# tick-box-1591A-mk-1_0.net
KiCad netlist of a schematic drawn in EAGLE
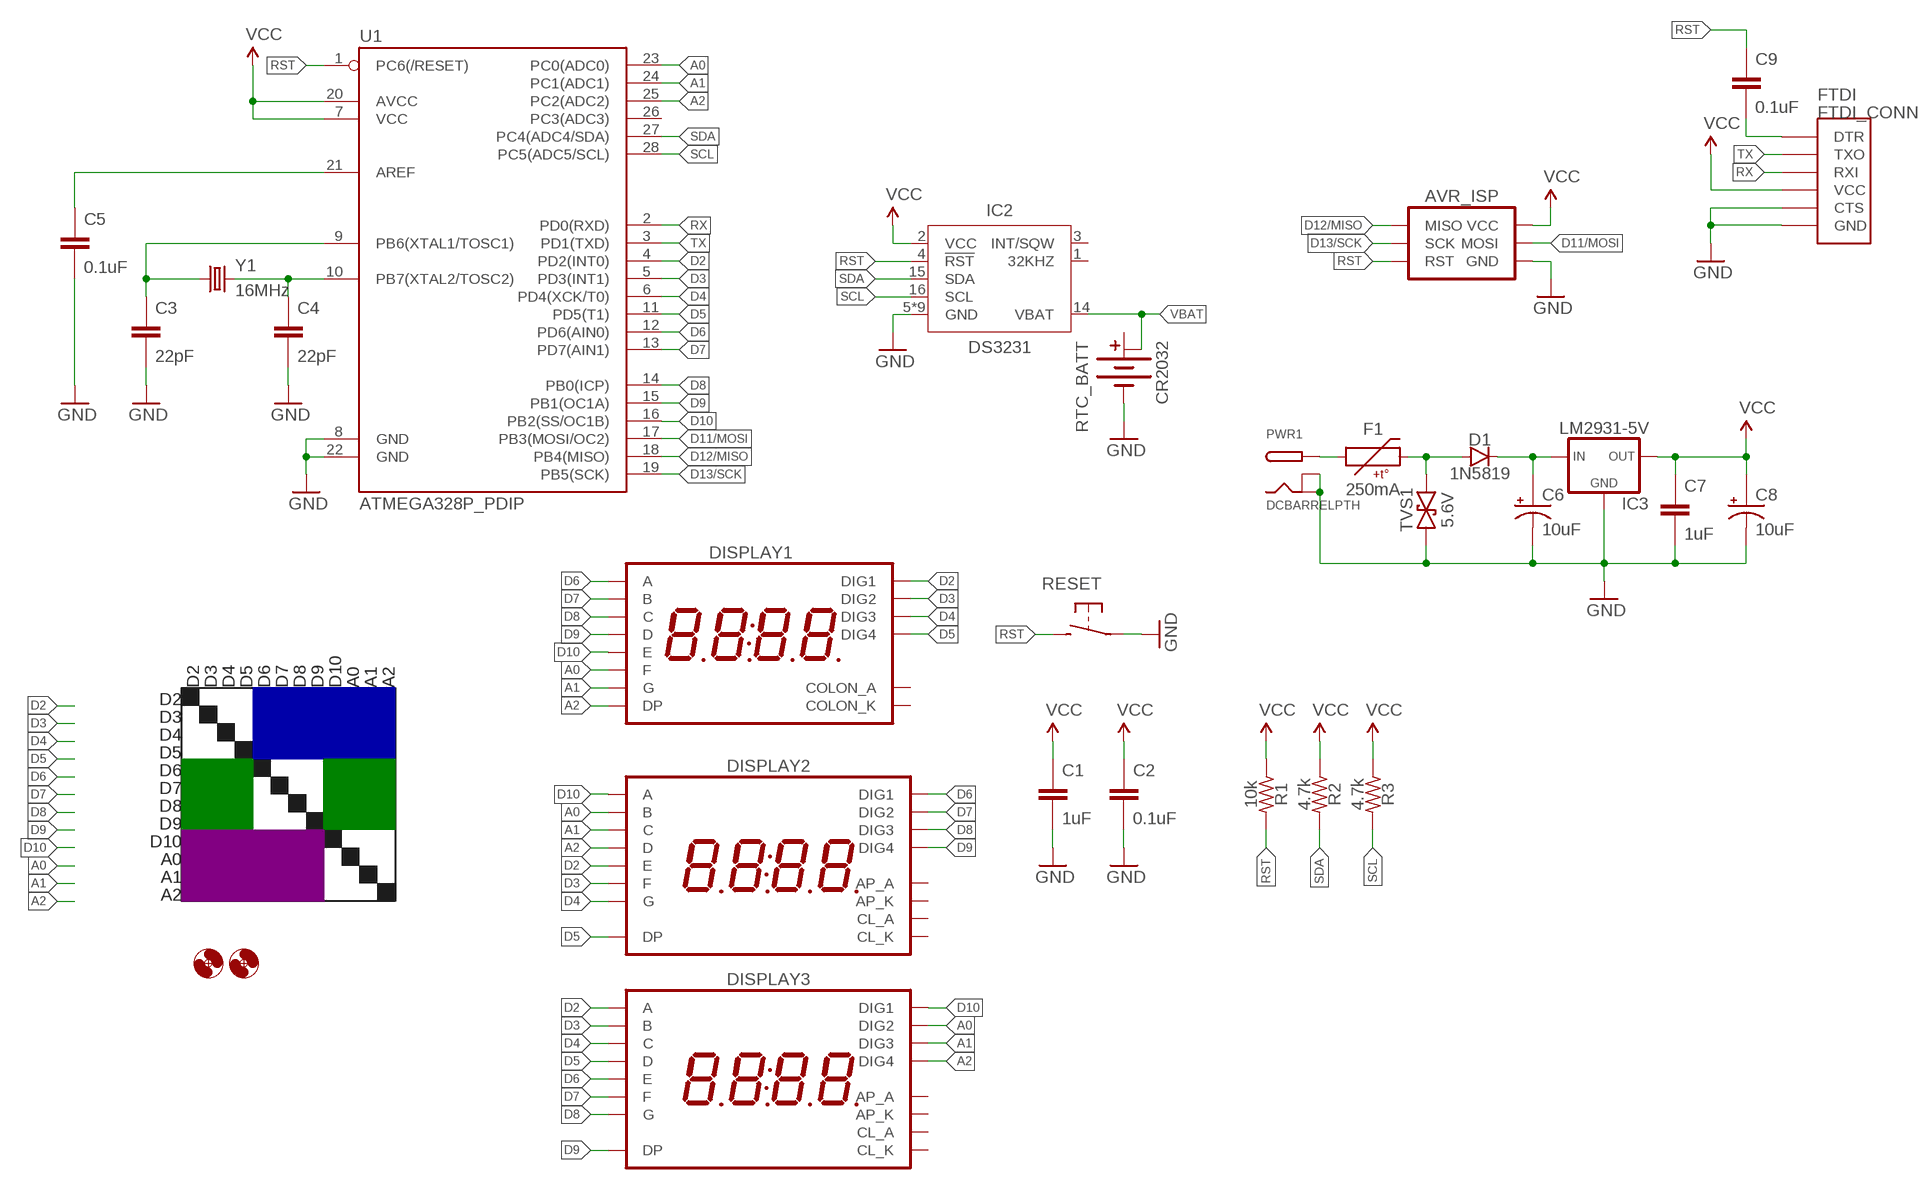
[diagram p0: schematic, sheet 1]

(export (version "E")
  (design (tool "Eeschema 10.0.6"))
  (components
    (comp (ref "AVR_ISP")
      (value "AVR_SPI_PRG_6PTH")
      (footprint "eagle-import:2X3")
      (libsource (lib "eagle-import") (part "AVR_SPI_PRG_6PTH"))
    )
    (comp (ref "C1")
      (value "1uF")
      (footprint "eagle-import:C025-024X044")
      (libsource (lib "eagle-import") (part "CAPACITOR-CERAMIC025-024X044"))
    )
    (comp (ref "C2")
      (value "0.1uF")
      (footprint "eagle-import:C025-024X044")
      (libsource (lib "eagle-import") (part "CAPACITOR-CERAMIC025-024X044"))
    )
    (comp (ref "C3")
      (value "22pF")
      (footprint "eagle-import:C025-024X044")
      (libsource (lib "eagle-import") (part "CAPACITOR-CERAMIC025-024X044"))
    )
    (comp (ref "C4")
      (value "22pF")
      (footprint "eagle-import:C025-024X044")
      (libsource (lib "eagle-import") (part "CAPACITOR-CERAMIC025-024X044"))
    )
    (comp (ref "C5")
      (value "0.1uF")
      (footprint "eagle-import:C025-024X044")
      (libsource (lib "eagle-import") (part "CAPACITOR-CERAMIC025-024X044"))
    )
    (comp (ref "C6")
      (value "10uF")
      (footprint "eagle-import:E2-5")
      (libsource (lib "eagle-import") (part "CAPACITOR-POLARIZEDE2-5"))
    )
    (comp (ref "C7")
      (value "1uF")
      (footprint "eagle-import:C025-024X044")
      (libsource (lib "eagle-import") (part "CAPACITOR-CERAMIC025-024X044"))
    )
    (comp (ref "C8")
      (value "10uF")
      (footprint "eagle-import:E2-5")
      (libsource (lib "eagle-import") (part "CAPACITOR-POLARIZEDE2-5"))
    )
    (comp (ref "C9")
      (value "0.1uF")
      (footprint "eagle-import:C025-024X044")
      (libsource (lib "eagle-import") (part "CAPACITOR-CERAMIC025-024X044"))
    )
    (comp (ref "D1")
      (value "1N5819")
      (footprint "eagle-import:DIODE-10.16MM")
      (libsource (lib "eagle-import") (part "DIODEPTH-10.68MM"))
    )
    (comp (ref "DISPLAY1")
      (value "7SEG_4DIGIT_COLON14.2MM-CC-NS")
      (footprint "eagle-import:7SEG_4DIG_NS")
      (libsource (lib "eagle-import") (part "7SEG_4DIGIT_COLON14.2MM-CC-NS"))
    )
    (comp (ref "DISPLAY2")
      (value "7SEG_4DIGIT_COLON_APOS")
      (footprint "eagle-import:7SEG_4DIG_10MM")
      (libsource (lib "eagle-import") (part "7SEG_4DIGIT_COLON_APOS"))
    )
    (comp (ref "DISPLAY3")
      (value "7SEG_4DIGIT_COLON_APOS")
      (footprint "eagle-import:7SEG_4DIG_10MM")
      (libsource (lib "eagle-import") (part "7SEG_4DIGIT_COLON_APOS"))
    )
    (comp (ref "F1")
      (value "250mA")
      (footprint "eagle-import:PTC-PTH-5.08MM")
      (libsource (lib "eagle-import") (part "PTCPTH-5.08MM"))
    )
    (comp (ref "FTDI")
      (value "FTDI_CONN")
      (footprint "eagle-import:FTDI_CONN")
      (libsource (lib "eagle-import") (part "FTDI_CONN"))
    )
    (comp (ref "H1")
      (value "HOLE#2")
      (footprint "eagle-import:HOLE-#2")
      (libsource (lib "eagle-import") (part "HOLE#2"))
    )
    (comp (ref "H2")
      (value "HOLE#2")
      (footprint "eagle-import:HOLE-#2")
      (libsource (lib "eagle-import") (part "HOLE#2"))
    )
    (comp (ref "IC2")
      (value "DS3231")
      (footprint "eagle-import:SO16W")
      (libsource (lib "eagle-import") (part "DS3231"))
    )
    (comp (ref "IC3")
      (value "LM2931-5V")
      (footprint "eagle-import:TO-92-AMMO")
      (libsource (lib "eagle-import") (part "V_REG_78XXTO-92-INLINE"))
    )
    (comp (ref "PWR1")
      (value "DCBARRELPTH")
      (footprint "eagle-import:DCJACK_2MM_PTH")
      (libsource (lib "eagle-import") (part "DCBARRELPTH"))
    )
    (comp (ref "R1")
      (value "10k")
      (footprint "eagle-import:RESISTOR-AXIAL-PTH-7.62MM")
      (libsource (lib "eagle-import") (part "RESISTORPTH-AXIAL-7.62MM"))
    )
    (comp (ref "R2")
      (value "4.7k")
      (footprint "eagle-import:RESISTOR-AXIAL-PTH-7.62MM")
      (libsource (lib "eagle-import") (part "RESISTORPTH-AXIAL-7.62MM"))
    )
    (comp (ref "R3")
      (value "4.7k")
      (footprint "eagle-import:RESISTOR-AXIAL-PTH-7.62MM")
      (libsource (lib "eagle-import") (part "RESISTORPTH-AXIAL-7.62MM"))
    )
    (comp (ref "RESET")
      (value "SPST-NO-TACT6MM-PTH-SMALL-PADS")
      (footprint "eagle-import:DTS-6-SMALL-PADS")
      (libsource (lib "eagle-import") (part "SPST-NO-TACT6MM-PTH-SMALL-PADS"))
    )
    (comp (ref "RTC_BATT")
      (value "CR2032")
      (footprint "eagle-import:BATTCON_20MM_MINE")
      (libsource (lib "eagle-import") (part "BATTERY-COINCR2032_SMD"))
    )
    (comp (ref "TVS1")
      (value "5.6V")
      (footprint "eagle-import:DO-41-TVS")
      (libsource (lib "eagle-import") (part "TVSDO-41-TVS-BIDIRECTIONAL"))
    )
    (comp (ref "U1")
      (value "ATMEGA328P_PDIP")
      (footprint "eagle-import:DIL28-3")
      (libsource (lib "eagle-import") (part "ATMEGA328P_PDIP"))
    )
    (comp (ref "Y1")
      (value "16MHz")
      (footprint "eagle-import:HC49U-V")
      (libsource (lib "eagle-import") (part "CRYSTALHC49UV"))
    )
  )
  (nets
    (net (code "1") (name "A0") (class "Default")
      (node (ref "DISPLAY1") (pin "P$12") (pinfunction "F_P$12") (pintype "passive"))
      (node (ref "DISPLAY2") (pin "16") (pinfunction "B_16") (pintype "passive"))
      (node (ref "DISPLAY3") (pin "2") (pinfunction "DIG2_2") (pintype "passive"))
      (node (ref "U1") (pin "23") (pinfunction "PC0(ADC0)_23") (pintype "bidirectional"))
    )
    (net (code "2") (name "A1") (class "Default")
      (node (ref "DISPLAY1") (pin "P$5") (pinfunction "G_P$5") (pintype "passive"))
      (node (ref "DISPLAY2") (pin "13") (pinfunction "C_13") (pintype "passive"))
      (node (ref "DISPLAY3") (pin "6") (pinfunction "DIG3_6") (pintype "passive"))
      (node (ref "U1") (pin "24") (pinfunction "PC1(ADC1)_24") (pintype "bidirectional"))
    )
    (net (code "3") (name "A2") (class "Default")
      (node (ref "DISPLAY1") (pin "P$3") (pinfunction "DP_P$3") (pintype "passive"))
      (node (ref "DISPLAY2") (pin "3") (pinfunction "D_3") (pintype "passive"))
      (node (ref "DISPLAY3") (pin "8") (pinfunction "DIG4_8") (pintype "passive"))
      (node (ref "U1") (pin "25") (pinfunction "PC2(ADC2)_25") (pintype "bidirectional"))
    )
    (net (code "4") (name "D2") (class "Default")
      (node (ref "DISPLAY1") (pin "P$14") (pinfunction "DIG1_P$14") (pintype "passive"))
      (node (ref "DISPLAY2") (pin "5") (pinfunction "E_5") (pintype "passive"))
      (node (ref "DISPLAY3") (pin "14") (pinfunction "A_14") (pintype "passive"))
      (node (ref "U1") (pin "4") (pinfunction "PD2(INT0)_4") (pintype "bidirectional"))
    )
    (net (code "5") (name "D3") (class "Default")
      (node (ref "DISPLAY1") (pin "P$11") (pinfunction "DIG2_P$11") (pintype "passive"))
      (node (ref "DISPLAY2") (pin "11") (pinfunction "F_11") (pintype "passive"))
      (node (ref "DISPLAY3") (pin "16") (pinfunction "B_16") (pintype "passive"))
      (node (ref "U1") (pin "5") (pinfunction "PD3(INT1)_5") (pintype "bidirectional"))
    )
    (net (code "6") (name "D4") (class "Default")
      (node (ref "DISPLAY1") (pin "P$10") (pinfunction "DIG3_P$10") (pintype "passive"))
      (node (ref "DISPLAY2") (pin "15") (pinfunction "G_15") (pintype "passive"))
      (node (ref "DISPLAY3") (pin "13") (pinfunction "C_13") (pintype "passive"))
      (node (ref "U1") (pin "6") (pinfunction "PD4(XCK/T0)_6") (pintype "bidirectional"))
    )
    (net (code "7") (name "D5") (class "Default")
      (node (ref "DISPLAY1") (pin "P$6") (pinfunction "DIG4_P$6") (pintype "passive"))
      (node (ref "DISPLAY2") (pin "7") (pinfunction "DP_7") (pintype "passive"))
      (node (ref "DISPLAY3") (pin "3") (pinfunction "D_3") (pintype "passive"))
      (node (ref "U1") (pin "11") (pinfunction "PD5(T1)_11") (pintype "bidirectional"))
    )
    (net (code "8") (name "D6") (class "Default")
      (node (ref "DISPLAY1") (pin "P$13") (pinfunction "A_P$13") (pintype "passive"))
      (node (ref "DISPLAY2") (pin "1") (pinfunction "DIG1_1") (pintype "passive"))
      (node (ref "DISPLAY3") (pin "5") (pinfunction "E_5") (pintype "passive"))
      (node (ref "U1") (pin "12") (pinfunction "PD6(AIN0)_12") (pintype "bidirectional"))
    )
    (net (code "9") (name "D7") (class "Default")
      (node (ref "DISPLAY1") (pin "P$9") (pinfunction "B_P$9") (pintype "passive"))
      (node (ref "DISPLAY2") (pin "2") (pinfunction "DIG2_2") (pintype "passive"))
      (node (ref "DISPLAY3") (pin "11") (pinfunction "F_11") (pintype "passive"))
      (node (ref "U1") (pin "13") (pinfunction "PD7(AIN1)_13") (pintype "bidirectional"))
    )
    (net (code "10") (name "D8") (class "Default")
      (node (ref "DISPLAY1") (pin "P$4") (pinfunction "C_P$4") (pintype "passive"))
      (node (ref "DISPLAY2") (pin "6") (pinfunction "DIG3_6") (pintype "passive"))
      (node (ref "DISPLAY3") (pin "15") (pinfunction "G_15") (pintype "passive"))
      (node (ref "U1") (pin "14") (pinfunction "PB0(ICP)_14") (pintype "bidirectional"))
    )
    (net (code "11") (name "D9") (class "Default")
      (node (ref "DISPLAY1") (pin "P$2") (pinfunction "D_P$2") (pintype "passive"))
      (node (ref "DISPLAY2") (pin "8") (pinfunction "DIG4_8") (pintype "passive"))
      (node (ref "DISPLAY3") (pin "7") (pinfunction "DP_7") (pintype "passive"))
      (node (ref "U1") (pin "15") (pinfunction "PB1(OC1A)_15") (pintype "bidirectional"))
    )
    (net (code "12") (name "D10") (class "Default")
      (node (ref "DISPLAY1") (pin "P$1") (pinfunction "E_P$1") (pintype "passive"))
      (node (ref "DISPLAY2") (pin "14") (pinfunction "A_14") (pintype "passive"))
      (node (ref "DISPLAY3") (pin "1") (pinfunction "DIG1_1") (pintype "passive"))
      (node (ref "U1") (pin "16") (pinfunction "PB2(SS/OC1B)_16") (pintype "bidirectional"))
    )
    (net (code "13") (name "D11{slash}MOSI") (class "Default")
      (node (ref "AVR_ISP") (pin "4") (pinfunction "MOSI_4") (pintype "passive"))
      (node (ref "U1") (pin "17") (pinfunction "PB3(MOSI/OC2)_17") (pintype "bidirectional"))
    )
    (net (code "14") (name "D12{slash}MISO") (class "Default")
      (node (ref "AVR_ISP") (pin "1") (pinfunction "MISO_1") (pintype "passive"))
      (node (ref "U1") (pin "18") (pinfunction "PB4(MISO)_18") (pintype "bidirectional"))
    )
    (net (code "15") (name "D13{slash}SCK") (class "Default")
      (node (ref "AVR_ISP") (pin "3") (pinfunction "SCK_3") (pintype "passive"))
      (node (ref "U1") (pin "19") (pinfunction "PB5(SCK)_19") (pintype "bidirectional"))
    )
    (net (code "16") (name "GND") (class "Default")
      (node (ref "AVR_ISP") (pin "6") (pinfunction "GND_6") (pintype "passive"))
      (node (ref "C1") (pin "2") (pinfunction "2_2") (pintype "passive"))
      (node (ref "C2") (pin "2") (pinfunction "2_2") (pintype "passive"))
      (node (ref "C3") (pin "2") (pinfunction "2_2") (pintype "passive"))
      (node (ref "C4") (pin "2") (pinfunction "2_2") (pintype "passive"))
      (node (ref "C5") (pin "2") (pinfunction "2_2") (pintype "passive"))
      (node (ref "C6") (pin "-") (pinfunction "-_-") (pintype "passive"))
      (node (ref "C7") (pin "2") (pinfunction "2_2") (pintype "passive"))
      (node (ref "C8") (pin "-") (pinfunction "-_-") (pintype "passive"))
      (node (ref "FTDI") (pin "CTS") (pinfunction "CTS_CTS") (pintype "bidirectional"))
      (node (ref "FTDI") (pin "GND") (pinfunction "GND_GND") (pintype "bidirectional"))
      (node (ref "IC2") (pin "10") (pinfunction "GND_10") (pintype "bidirectional"))
      (node (ref "IC2") (pin "11") (pinfunction "GND_11") (pintype "bidirectional"))
      (node (ref "IC2") (pin "12") (pinfunction "GND_12") (pintype "bidirectional"))
      (node (ref "IC2") (pin "13") (pinfunction "GND_13") (pintype "bidirectional"))
      (node (ref "IC2") (pin "5") (pinfunction "GND_5") (pintype "bidirectional"))
      (node (ref "IC2") (pin "6") (pinfunction "GND_6") (pintype "bidirectional"))
      (node (ref "IC2") (pin "7") (pinfunction "GND_7") (pintype "bidirectional"))
      (node (ref "IC2") (pin "8") (pinfunction "GND_8") (pintype "bidirectional"))
      (node (ref "IC2") (pin "9") (pinfunction "GND_9") (pintype "bidirectional"))
      (node (ref "IC3") (pin "2") (pinfunction "GND_2") (pintype "bidirectional"))
      (node (ref "PWR1") (pin "BRK") (pinfunction "BRK_BRK") (pintype "bidirectional"))
      (node (ref "PWR1") (pin "GND") (pinfunction "GND_GND") (pintype "bidirectional"))
      (node (ref "RESET") (pin "1") (pinfunction "1_1") (pintype "passive"))
      (node (ref "RESET") (pin "2") (pinfunction "1_2") (pintype "passive"))
      (node (ref "RTC_BATT") (pin "BOTTOM") (pinfunction "-_BOTTOM") (pintype "bidirectional"))
      (node (ref "TVS1") (pin "P$1") (pinfunction "1_P$1") (pintype "passive"))
      (node (ref "U1") (pin "22") (pinfunction "GND_22") (pintype "bidirectional"))
      (node (ref "U1") (pin "8") (pinfunction "GND_8") (pintype "bidirectional"))
    )
    (net (code "17") (name "Net-(C9-Pad2)") (class "Default")
      (node (ref "C9") (pin "2") (pinfunction "2_2") (pintype "passive"))
      (node (ref "FTDI") (pin "DTR") (pinfunction "DTR_DTR") (pintype "bidirectional"))
    )
    (net (code "18") (name "Net-(F1-1)") (class "Default")
      (node (ref "F1") (pin "P$1") (pinfunction "1_P$1") (pintype "passive"))
      (node (ref "PWR1") (pin "PWR") (pinfunction "PWR_PWR") (pintype "bidirectional"))
    )
    (net (code "19") (name "Net-(F1-2)") (class "Default")
      (node (ref "D1") (pin "A") (pinfunction "A_A") (pintype "passive"))
      (node (ref "F1") (pin "P$2") (pinfunction "2_P$2") (pintype "passive"))
      (node (ref "TVS1") (pin "P$2") (pinfunction "2_P$2") (pintype "passive"))
    )
    (net (code "20") (name "Net-(IC3-IN)") (class "Default")
      (node (ref "C6") (pin "+") (pinfunction "+_+") (pintype "passive"))
      (node (ref "D1") (pin "C") (pinfunction "C_C") (pintype "passive"))
      (node (ref "IC3") (pin "1") (pinfunction "IN_1") (pintype "bidirectional"))
    )
    (net (code "21") (name "Net-(U1-AREF)") (class "Default")
      (node (ref "C5") (pin "1") (pinfunction "1_1") (pintype "passive"))
      (node (ref "U1") (pin "21") (pinfunction "AREF_21") (pintype "bidirectional"))
    )
    (net (code "22") (name "Net-(U1-PB6(XTAL1{slash}TOSC1))") (class "Default")
      (node (ref "C3") (pin "1") (pinfunction "1_1") (pintype "passive"))
      (node (ref "U1") (pin "9") (pinfunction "PB6(XTAL1/TOSC1)_9") (pintype "bidirectional"))
      (node (ref "Y1") (pin "1") (pinfunction "1_1") (pintype "passive"))
    )
    (net (code "23") (name "Net-(U1-PB7(XTAL2{slash}TOSC2))") (class "Default")
      (node (ref "C4") (pin "1") (pinfunction "1_1") (pintype "passive"))
      (node (ref "U1") (pin "10") (pinfunction "PB7(XTAL2/TOSC2)_10") (pintype "bidirectional"))
      (node (ref "Y1") (pin "2") (pinfunction "2_2") (pintype "passive"))
    )
    (net (code "24") (name "RST") (class "Default")
      (node (ref "AVR_ISP") (pin "5") (pinfunction "RST_5") (pintype "passive"))
      (node (ref "C9") (pin "1") (pinfunction "1_1") (pintype "passive"))
      (node (ref "IC2") (pin "4") (pinfunction "~{RST}_4") (pintype "bidirectional"))
      (node (ref "R1") (pin "P$2") (pinfunction "2_P$2") (pintype "passive"))
      (node (ref "RESET") (pin "3") (pinfunction "2_3") (pintype "passive"))
      (node (ref "RESET") (pin "4") (pinfunction "2_4") (pintype "passive"))
      (node (ref "U1") (pin "1") (pinfunction "PC6(/RESET)_1") (pintype "bidirectional"))
    )
    (net (code "25") (name "RX") (class "Default")
      (node (ref "FTDI") (pin "RXI") (pinfunction "RXI_RXI") (pintype "bidirectional"))
      (node (ref "U1") (pin "2") (pinfunction "PD0(RXD)_2") (pintype "bidirectional"))
    )
    (net (code "26") (name "SCL") (class "Default")
      (node (ref "IC2") (pin "16") (pinfunction "SCL_16") (pintype "bidirectional"))
      (node (ref "R3") (pin "P$2") (pinfunction "2_P$2") (pintype "passive"))
      (node (ref "U1") (pin "28") (pinfunction "PC5(ADC5/SCL)_28") (pintype "bidirectional"))
    )
    (net (code "27") (name "SDA") (class "Default")
      (node (ref "IC2") (pin "15") (pinfunction "SDA_15") (pintype "bidirectional"))
      (node (ref "R2") (pin "P$2") (pinfunction "2_P$2") (pintype "passive"))
      (node (ref "U1") (pin "27") (pinfunction "PC4(ADC4/SDA)_27") (pintype "bidirectional"))
    )
    (net (code "28") (name "TX") (class "Default")
      (node (ref "FTDI") (pin "TXO") (pinfunction "TXO_TXO") (pintype "bidirectional"))
      (node (ref "U1") (pin "3") (pinfunction "PD1(TXD)_3") (pintype "bidirectional"))
    )
    (net (code "29") (name "VBAT") (class "Default")
      (node (ref "IC2") (pin "14") (pinfunction "VBAT_14") (pintype "bidirectional"))
      (node (ref "RTC_BATT") (pin "TOP@2") (pinfunction "+1_TOP@2") (pintype "bidirectional"))
    )
    (net (code "30") (name "VCC") (class "Default")
      (node (ref "AVR_ISP") (pin "2") (pinfunction "VCC_2") (pintype "passive"))
      (node (ref "C1") (pin "1") (pinfunction "1_1") (pintype "passive"))
      (node (ref "C2") (pin "1") (pinfunction "1_1") (pintype "passive"))
      (node (ref "C7") (pin "1") (pinfunction "1_1") (pintype "passive"))
      (node (ref "C8") (pin "+") (pinfunction "+_+") (pintype "passive"))
      (node (ref "FTDI") (pin "VCC") (pinfunction "VCC_VCC") (pintype "bidirectional"))
      (node (ref "IC2") (pin "2") (pinfunction "VCC_2") (pintype "bidirectional"))
      (node (ref "IC3") (pin "3") (pinfunction "OUT_3") (pintype "bidirectional"))
      (node (ref "R1") (pin "P$1") (pinfunction "1_P$1") (pintype "passive"))
      (node (ref "R2") (pin "P$1") (pinfunction "1_P$1") (pintype "passive"))
      (node (ref "R3") (pin "P$1") (pinfunction "1_P$1") (pintype "passive"))
      (node (ref "U1") (pin "20") (pinfunction "AVCC_20") (pintype "bidirectional"))
      (node (ref "U1") (pin "7") (pinfunction "VCC_7") (pintype "bidirectional"))
    )
    (net (code "31") (name "unconnected-(DISPLAY1-COLON_A-PadP$8)") (class "Default")
      (node (ref "DISPLAY1") (pin "P$8") (pinfunction "COLON_A_P$8") (pintype "passive"))
    )
    (net (code "32") (name "unconnected-(DISPLAY1-COLON_K-PadP$7)") (class "Default")
      (node (ref "DISPLAY1") (pin "P$7") (pinfunction "COLON_K_P$7") (pintype "passive"))
    )
    (net (code "33") (name "unconnected-(DISPLAY2-AP_A-Pad10)") (class "Default")
      (node (ref "DISPLAY2") (pin "10") (pinfunction "AP_A_10") (pintype "bidirectional"))
    )
    (net (code "34") (name "unconnected-(DISPLAY2-AP_K-Pad9)") (class "Default")
      (node (ref "DISPLAY2") (pin "9") (pinfunction "AP_K_9") (pintype "bidirectional"))
    )
    (net (code "35") (name "unconnected-(DISPLAY2-CL_A-Pad4)") (class "Default")
      (node (ref "DISPLAY2") (pin "4") (pinfunction "CL_A_4") (pintype "passive"))
    )
    (net (code "36") (name "unconnected-(DISPLAY2-CL_K-Pad12)") (class "Default")
      (node (ref "DISPLAY2") (pin "12") (pinfunction "CL_K_12") (pintype "passive"))
    )
    (net (code "37") (name "unconnected-(DISPLAY3-AP_A-Pad10)") (class "Default")
      (node (ref "DISPLAY3") (pin "10") (pinfunction "AP_A_10") (pintype "bidirectional"))
    )
    (net (code "38") (name "unconnected-(DISPLAY3-AP_K-Pad9)") (class "Default")
      (node (ref "DISPLAY3") (pin "9") (pinfunction "AP_K_9") (pintype "bidirectional"))
    )
    (net (code "39") (name "unconnected-(DISPLAY3-CL_A-Pad4)") (class "Default")
      (node (ref "DISPLAY3") (pin "4") (pinfunction "CL_A_4") (pintype "passive"))
    )
    (net (code "40") (name "unconnected-(DISPLAY3-CL_K-Pad12)") (class "Default")
      (node (ref "DISPLAY3") (pin "12") (pinfunction "CL_K_12") (pintype "passive"))
    )
    (net (code "41") (name "unconnected-(IC2-32KHZ-Pad1)") (class "Default")
      (node (ref "IC2") (pin "1") (pinfunction "32KHZ_1") (pintype "bidirectional"))
    )
    (net (code "42") (name "unconnected-(IC2-INT{slash}SQW-Pad3)") (class "Default")
      (node (ref "IC2") (pin "3") (pinfunction "INT/SQW_3") (pintype "bidirectional"))
    )
    (net (code "43") (name "unconnected-(RTC_BATT-+-PadTOP@1)") (class "Default")
      (node (ref "RTC_BATT") (pin "TOP@1") (pinfunction "+_TOP@1") (pintype "bidirectional"))
    )
    (net (code "44") (name "unconnected-(U1-PC3(ADC3)-Pad26)") (class "Default")
      (node (ref "U1") (pin "26") (pinfunction "PC3(ADC3)_26") (pintype "bidirectional"))
    )
  )
)
